# 05_RTC_RS232_USB.net
KiCad netlist of a schematic drawn in Altium Designer
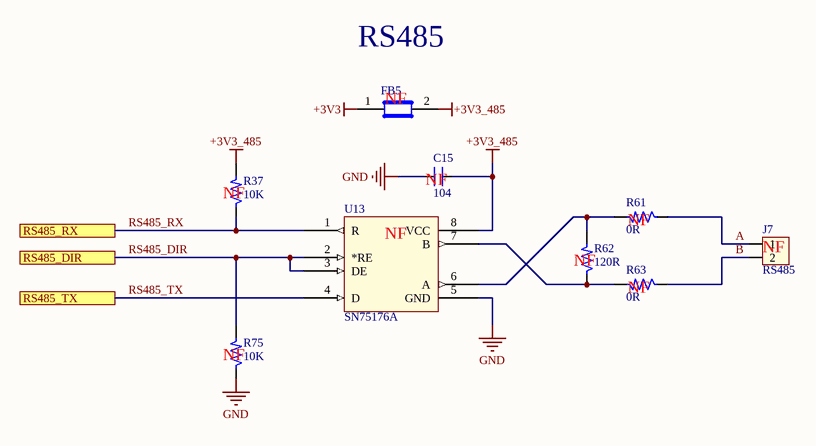
[diagram p0: [05] RTC_RS232_USB.SchDoc]

(export (version "E")
  (design (tool "Eeschema 10.0.6"))
  (components
    (comp (ref "C15")
      (value "104")
      (footprint "C0603 SMT")
      (description "Cap SMD")
      (libsource (lib "khapham") (part "CM"))
    )
    (comp (ref "FB5")
      (value "BLM21PG600SN1D")
      (footprint "R0805")
      (description "Ferrite Bead")
      (libsource (lib "khapham") (part "Ferrite Bead"))
    )
    (comp (ref "J7")
      (value "RS485")
      (footprint "Hed2V_3.96")
      (description "Header 2 (Green)")
      (libsource (lib "khapham") (part "Hed2"))
    )
    (comp (ref "R37")
      (value "10K")
      (footprint "R0603 -SMT")
      (description "Resistor SMD")
      (libsource (lib "khapham") (part "RM"))
    )
    (comp (ref "R61")
      (value "0R")
      (footprint "R0603 -SMT")
      (description "Resistor SMD")
      (libsource (lib "khapham") (part "RM"))
    )
    (comp (ref "R62")
      (value "120R")
      (footprint "R0603 -SMT")
      (description "Resistor SMD")
      (libsource (lib "khapham") (part "RM"))
    )
    (comp (ref "R63")
      (value "0R")
      (footprint "R0603 -SMT")
      (description "Resistor SMD")
      (libsource (lib "khapham") (part "RM"))
    )
    (comp (ref "R75")
      (value "10K")
      (footprint "R0603 -SMT")
      (description "Resistor SMD")
      (libsource (lib "khapham") (part "RM"))
    )
    (comp (ref "U13")
      (value "SN75176A")
      (footprint "SN75176A")
      (libsource (lib "mlab_lib") (part "SN75176A"))
    )
  )
  (nets
    (net (code "1") (name "+3V3") (class "Default")
      (node (ref "FB5") (pin "1") (pinfunction "1_1") (pintype "passive"))
    )
    (net (code "2") (name "+3V3_485") (class "Default")
      (node (ref "C15") (pin "2") (pinfunction "2_2") (pintype "passive"))
      (node (ref "FB5") (pin "2") (pinfunction "2_2") (pintype "passive"))
      (node (ref "R37") (pin "2") (pinfunction "2_2") (pintype "passive"))
      (node (ref "U13") (pin "8") (pinfunction "VCC_8") (pintype "power_in"))
    )
    (net (code "3") (name "/A") (class "Default")
      (node (ref "J7") (pin "1") (pinfunction "1_1") (pintype "passive"))
      (node (ref "R61") (pin "1") (pinfunction "1_1") (pintype "passive"))
    )
    (net (code "4") (name "/B") (class "Default")
      (node (ref "J7") (pin "2") (pinfunction "2_2") (pintype "passive"))
      (node (ref "R63") (pin "1") (pinfunction "1_1") (pintype "passive"))
    )
    (net (code "5") (name "/RS485_DIR") (class "Default")
      (node (ref "R75") (pin "2") (pinfunction "2_2") (pintype "passive"))
      (node (ref "U13") (pin "2") (pinfunction "*RE_2") (pintype "input"))
      (node (ref "U13") (pin "3") (pinfunction "DE_3") (pintype "input"))
    )
    (net (code "6") (name "/RS485_RX") (class "Default")
      (node (ref "R37") (pin "1") (pinfunction "1_1") (pintype "passive"))
      (node (ref "U13") (pin "1") (pinfunction "R_1") (pintype "output"))
    )
    (net (code "7") (name "/RS485_TX") (class "Default")
      (node (ref "U13") (pin "4") (pinfunction "D_4") (pintype "input"))
    )
    (net (code "8") (name "GND") (class "Default")
      (node (ref "C15") (pin "1") (pinfunction "1_1") (pintype "passive"))
      (node (ref "R75") (pin "1") (pinfunction "1_1") (pintype "passive"))
      (node (ref "U13") (pin "5") (pinfunction "GND_5") (pintype "power_in"))
    )
    (net (code "9") (name "Net-(U13-A)") (class "Default")
      (node (ref "R61") (pin "2") (pinfunction "2_2") (pintype "passive"))
      (node (ref "R62") (pin "2") (pinfunction "2_2") (pintype "passive"))
      (node (ref "U13") (pin "6") (pinfunction "A_6") (pintype "output"))
    )
    (net (code "10") (name "Net-(U13-B)") (class "Default")
      (node (ref "R62") (pin "1") (pinfunction "1_1") (pintype "passive"))
      (node (ref "R63") (pin "2") (pinfunction "2_2") (pintype "passive"))
      (node (ref "U13") (pin "7") (pinfunction "B_7") (pintype "output"))
    )
  )
)
